# Client_Sheet3.net
KiCad netlist of a schematic drawn in Altium Designer
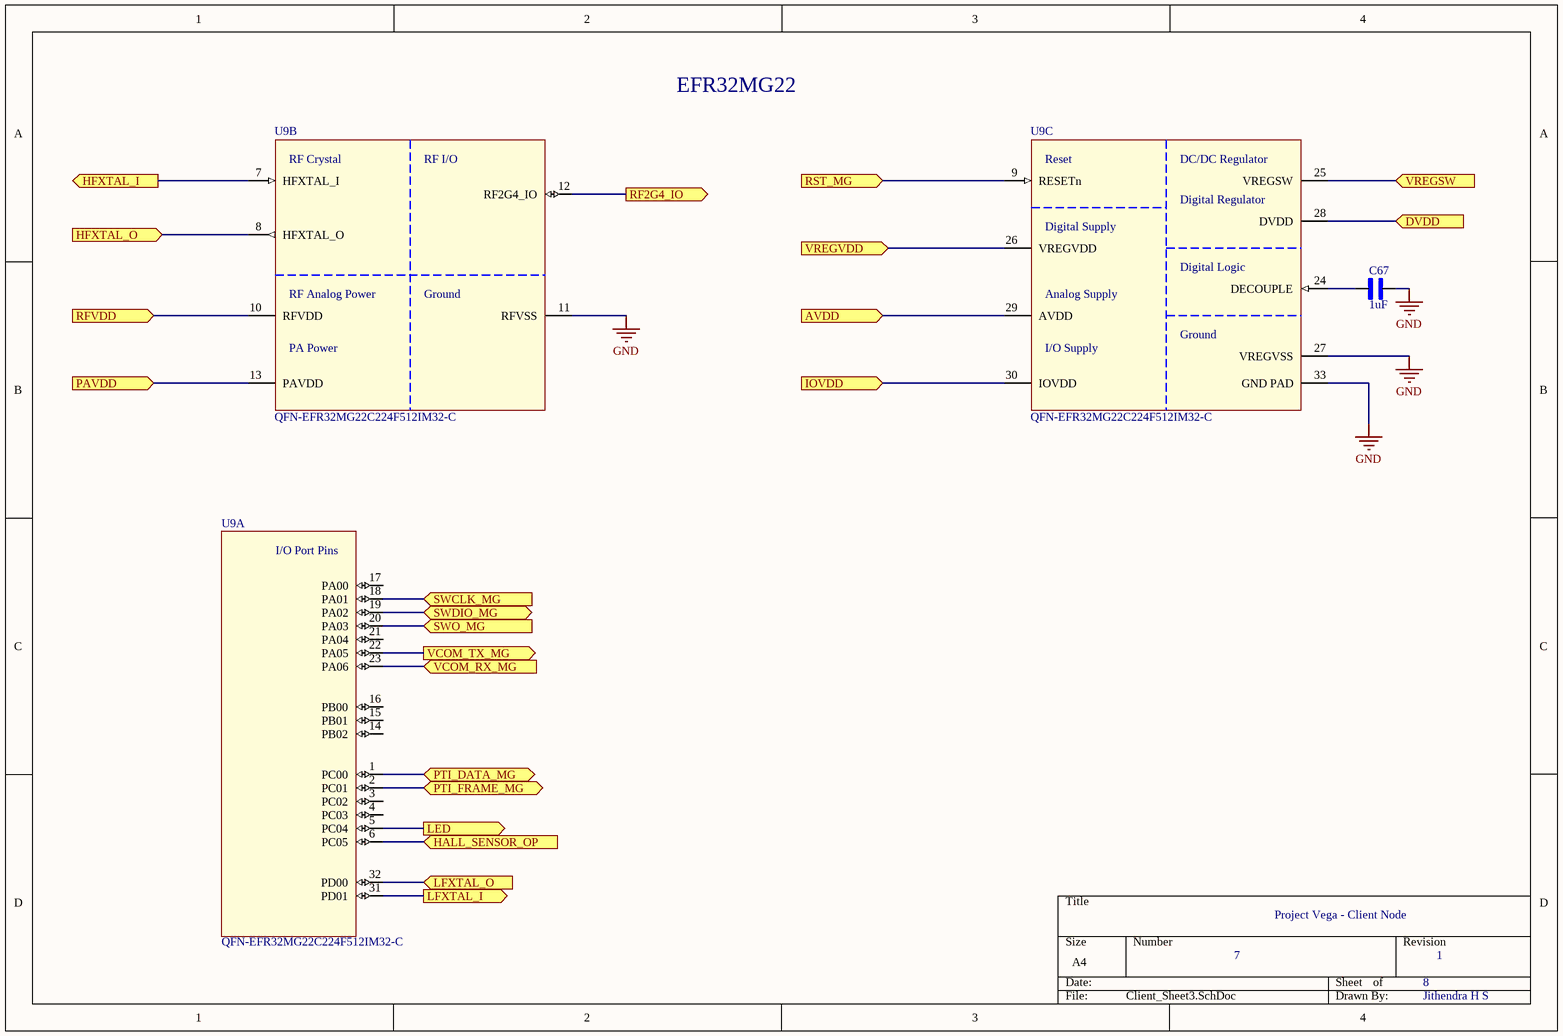
[diagram p0: Client_Sheet3.SchDoc]

(export (version "E")
  (design (tool "Eeschema 10.0.6"))
  (components
    (comp (ref "C67")
      (value "1uF")
      (footprint "CAPC1608X90")
      (description "0.1 ÂµF Â±10% 50V Ceramic Capacitor X7R 0603 (1608 Metric)")
      (fields (field (name "MF") "Yageo") (field (name "MP") "CC0603KRX7R9BB104"))
      (libsource (lib "Project_Vega") (part "CC0603KRX7R9BB104"))
    )
    (comp (ref "U9")
      (value "QFN-EFR32MG22C224F512IM32-C")
      (footprint "QFN32-EFR32xG2xIM32-BR")
      (description "IC RF TxRx + MCU WiFi Bluetooth v5.2, Zigbee® 2.4GHz 32-VFQFN Exposed Pad")
      (libsource (lib "Project_Vega") (part "EFR32MG22C224F512IM32-C"))
    )
  )
  (nets
    (net (code "1") (name "/AVDD") (class "Default")
      (node (ref "U9") (pin "29") (pinfunction "AVDD_29") (pintype "power_in"))
    )
    (net (code "2") (name "/DVDD") (class "Default")
      (node (ref "U9") (pin "28") (pinfunction "DVDD_28") (pintype "power_in"))
    )
    (net (code "3") (name "/HALL_SENSOR_OP") (class "Default")
      (node (ref "U9") (pin "6") (pinfunction "PC05_6") (pintype "bidirectional"))
    )
    (net (code "4") (name "/HFXTAL_I") (class "Default")
      (node (ref "U9") (pin "7") (pinfunction "HFXTAL_I_7") (pintype "input"))
    )
    (net (code "5") (name "/HFXTAL_O") (class "Default")
      (node (ref "U9") (pin "8") (pinfunction "HFXTAL_O_8") (pintype "output"))
    )
    (net (code "6") (name "/IOVDD") (class "Default")
      (node (ref "U9") (pin "30") (pinfunction "IOVDD_30") (pintype "power_in"))
    )
    (net (code "7") (name "/LED") (class "Default")
      (node (ref "U9") (pin "5") (pinfunction "PC04_5") (pintype "bidirectional"))
    )
    (net (code "8") (name "/LFXTAL_I") (class "Default")
      (node (ref "U9") (pin "31") (pinfunction "PD01_31") (pintype "bidirectional"))
    )
    (net (code "9") (name "/LFXTAL_O") (class "Default")
      (node (ref "U9") (pin "32") (pinfunction "PD00_32") (pintype "bidirectional"))
    )
    (net (code "10") (name "/PAVDD") (class "Default")
      (node (ref "U9") (pin "13") (pinfunction "PAVDD_13") (pintype "power_in"))
    )
    (net (code "11") (name "/PTI_DATA_MG") (class "Default")
      (node (ref "U9") (pin "1") (pinfunction "PC00_1") (pintype "bidirectional"))
    )
    (net (code "12") (name "/PTI_FRAME_MG") (class "Default")
      (node (ref "U9") (pin "2") (pinfunction "PC01_2") (pintype "bidirectional"))
    )
    (net (code "13") (name "/RF2G4_IO") (class "Default")
      (node (ref "U9") (pin "12") (pinfunction "RF2G4_IO_12") (pintype "bidirectional"))
    )
    (net (code "14") (name "/RFVDD") (class "Default")
      (node (ref "U9") (pin "10") (pinfunction "RFVDD_10") (pintype "power_in"))
    )
    (net (code "15") (name "/RST_MG") (class "Default")
      (node (ref "U9") (pin "9") (pinfunction "RESETn_9") (pintype "input"))
    )
    (net (code "16") (name "/SWCLK_MG") (class "Default")
      (node (ref "U9") (pin "18") (pinfunction "PA01_18") (pintype "bidirectional"))
    )
    (net (code "17") (name "/SWDIO_MG") (class "Default")
      (node (ref "U9") (pin "19") (pinfunction "PA02_19") (pintype "bidirectional"))
    )
    (net (code "18") (name "/SWO_MG") (class "Default")
      (node (ref "U9") (pin "20") (pinfunction "PA03_20") (pintype "bidirectional"))
    )
    (net (code "19") (name "/VCOM_RX_MG") (class "Default")
      (node (ref "U9") (pin "23") (pinfunction "PA06_23") (pintype "bidirectional"))
    )
    (net (code "20") (name "/VCOM_TX_MG") (class "Default")
      (node (ref "U9") (pin "22") (pinfunction "PA05_22") (pintype "bidirectional"))
    )
    (net (code "21") (name "/VREGSW") (class "Default")
      (node (ref "U9") (pin "25") (pinfunction "VREGSW_25") (pintype "power_in"))
    )
    (net (code "22") (name "/VREGVDD") (class "Default")
      (node (ref "U9") (pin "26") (pinfunction "VREGVDD_26") (pintype "power_in"))
    )
    (net (code "23") (name "GND") (class "Default")
      (node (ref "C67") (pin "2") (pinfunction "2_2") (pintype "passive"))
      (node (ref "U9") (pin "11") (pinfunction "RFVSS_11") (pintype "power_in"))
      (node (ref "U9") (pin "27") (pinfunction "VREGVSS_27") (pintype "power_in"))
      (node (ref "U9") (pin "33") (pinfunction "GND_PAD_33") (pintype "power_in"))
    )
    (net (code "24") (name "Net-(U9C-DECOUPLE)") (class "Default")
      (node (ref "C67") (pin "1") (pinfunction "1_1") (pintype "passive"))
      (node (ref "U9") (pin "24") (pinfunction "DECOUPLE_24") (pintype "input"))
    )
    (net (code "25") (name "unconnected-(U9A-PA00-Pad17)") (class "Default")
      (node (ref "U9") (pin "17") (pinfunction "PA00_17") (pintype "bidirectional"))
    )
    (net (code "26") (name "unconnected-(U9A-PA04-Pad21)") (class "Default")
      (node (ref "U9") (pin "21") (pinfunction "PA04_21") (pintype "bidirectional"))
    )
    (net (code "27") (name "unconnected-(U9A-PB00-Pad16)") (class "Default")
      (node (ref "U9") (pin "16") (pinfunction "PB00_16") (pintype "bidirectional"))
    )
    (net (code "28") (name "unconnected-(U9A-PB01-Pad15)") (class "Default")
      (node (ref "U9") (pin "15") (pinfunction "PB01_15") (pintype "bidirectional"))
    )
    (net (code "29") (name "unconnected-(U9A-PB02-Pad14)") (class "Default")
      (node (ref "U9") (pin "14") (pinfunction "PB02_14") (pintype "bidirectional"))
    )
    (net (code "30") (name "unconnected-(U9A-PC02-Pad3)") (class "Default")
      (node (ref "U9") (pin "3") (pinfunction "PC02_3") (pintype "bidirectional"))
    )
    (net (code "31") (name "unconnected-(U9A-PC03-Pad4)") (class "Default")
      (node (ref "U9") (pin "4") (pinfunction "PC03_4") (pintype "bidirectional"))
    )
  )
)
